# Level-Translator.net
KiCad netlist of a schematic drawn in Altium Designer
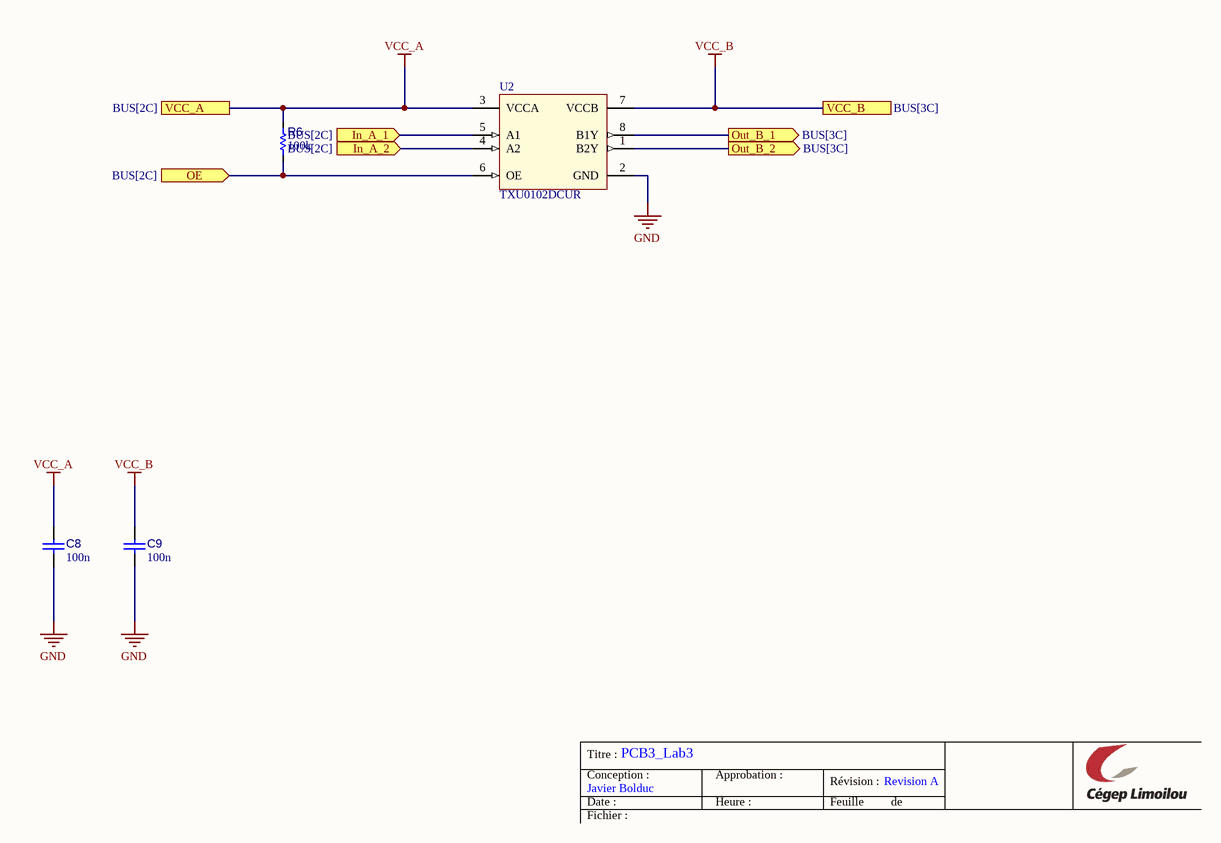
[diagram p0: Level-Translator.schdoc]

(export (version "E")
  (design (tool "Eeschema 10.0.6"))
  (components
    (comp (ref "C8")
      (value "100n")
      (footprint "C_1608[0603]")
      (description "Capacitor type 1")
      (fields (field (name "TOLERANCE") "10%") (field (name "Comment") "CAP CER 100nF 50V 0603"))
      (libsource (lib "TEP-AltiumLib-Passives-RLC") (part "capacitor"))
    )
    (comp (ref "C9")
      (value "100n")
      (footprint "C_1608[0603]")
      (description "Capacitor type 1")
      (fields (field (name "TOLERANCE") "10%") (field (name "Comment") "CAP CER 100nF 50V 0603"))
      (libsource (lib "TEP-AltiumLib-Passives-RLC") (part "capacitor"))
    )
    (comp (ref "R6")
      (value "100k")
      (footprint "R_1608[0603]")
      (description "Resistor type 1")
      (fields (field (name "TOLERANCE") "1%") (field (name "Comment") "Res 100k 1% 0603"))
      (libsource (lib "TEP-AltiumLib-Passives-RLC") (part "resistor"))
    )
    (comp (ref "U2")
      (value "TXU0102DCUR")
      (footprint "U_VSSOP50P310X200X90-8N")
      (description "Two channel fixed-direction level shifter 8-VSSOP")
      (libsource (lib "TEP-AltiumLib-ICs") (part "U_TXU0102DCU"))
    )
  )
  (nets
    (net (code "1") (name "/In_A_1") (class "Default")
      (node (ref "U2") (pin "5") (pinfunction "A1_5") (pintype "input"))
    )
    (net (code "2") (name "/In_A_2") (class "Default")
      (node (ref "U2") (pin "4") (pinfunction "A2_4") (pintype "input"))
    )
    (net (code "3") (name "/OE") (class "Default")
      (node (ref "R6") (pin "2") (pinfunction "2_2") (pintype "passive"))
      (node (ref "U2") (pin "6") (pinfunction "OE_6") (pintype "input"))
    )
    (net (code "4") (name "/Out_B_1") (class "Default")
      (node (ref "U2") (pin "8") (pinfunction "B1Y_8") (pintype "output"))
    )
    (net (code "5") (name "/Out_B_2") (class "Default")
      (node (ref "U2") (pin "1") (pinfunction "B2Y_1") (pintype "output"))
    )
    (net (code "6") (name "GND") (class "Default")
      (node (ref "C8") (pin "2") (pinfunction "2_2") (pintype "passive"))
      (node (ref "C9") (pin "2") (pinfunction "2_2") (pintype "passive"))
      (node (ref "U2") (pin "2") (pinfunction "GND_2") (pintype "power_in"))
    )
    (net (code "7") (name "VCC_A") (class "Default")
      (node (ref "C8") (pin "1") (pinfunction "1_1") (pintype "passive"))
      (node (ref "R6") (pin "1") (pinfunction "1_1") (pintype "passive"))
      (node (ref "U2") (pin "3") (pinfunction "VCCA_3") (pintype "power_in"))
    )
    (net (code "8") (name "VCC_B") (class "Default")
      (node (ref "C9") (pin "1") (pinfunction "1_1") (pintype "passive"))
      (node (ref "U2") (pin "7") (pinfunction "VCCB_7") (pintype "power_in"))
    )
  )
)
